# LEDBoard.net
KiCad netlist of a schematic drawn in Altium Designer
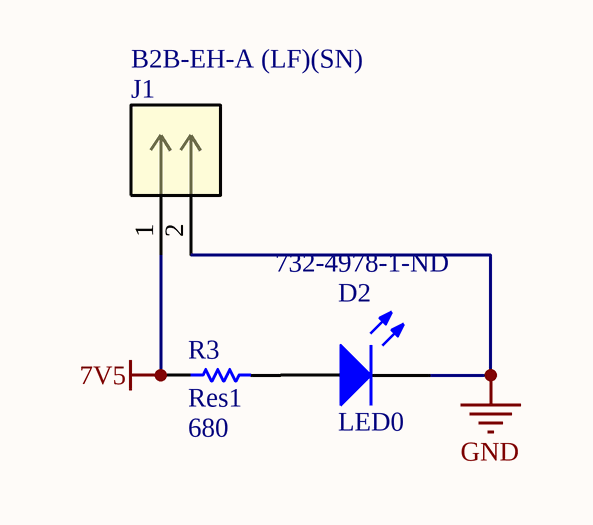
[diagram p0: LEDBoard.SchDoc]

(export (version "E")
  (design (tool "Eeschema 10.0.6"))
  (components
    (comp (ref "D2")
      (value "LED0")
      (footprint "1608[0603]")
      (description "Typical INFRARED GaAs LED")
      (fields
        (field (name "SUPPLIER PART NUMBER 1") "732-4978-1-ND")
        (field (name "PUBLISHER") "Altium Limited")
      )
      (libsource (lib "Miscellaneous Devices") (part "LED0"))
    )
    (comp (ref "J1")
      (value "B2B-EH-A (LF)(SN)")
      (footprint "CONN_B2B-EH-A (LF)(SN)_JST")
      (description "No Description Available")
      (fields (field (name "COPYRIGHT") "Copyright (C) 2018 Accelerated Designs. All rights reserved"))
      (libsource (lib "2020-09-22_22-27-35") (part "B2B-EH-A (LF)(SN)"))
    )
    (comp (ref "R3")
      (value "Res1")
      (footprint "6-0805_N")
      (description "Resistor")
      (fields (field (name "ALTIUM_VALUE") "680") (field (name "PUBLISHER") "Altium Limited"))
      (libsource (lib "Miscellaneous Devices") (part "Res1"))
    )
  )
  (nets
    (net (code "1") (name "7V5") (class "Default")
      (node (ref "J1") (pin "1") (pinfunction "1_1") (pintype "passive"))
      (node (ref "R3") (pin "1") (pinfunction "1_1") (pintype "passive"))
    )
    (net (code "2") (name "GND") (class "Default")
      (node (ref "D2") (pin "2") (pinfunction "K_2") (pintype "passive"))
      (node (ref "J1") (pin "2") (pinfunction "2_2") (pintype "passive"))
    )
    (net (code "3") (name "Net-(D2-A)") (class "Default")
      (node (ref "D2") (pin "1") (pinfunction "A_1") (pintype "passive"))
      (node (ref "R3") (pin "2") (pinfunction "2_2") (pintype "passive"))
    )
  )
)
